# phase90.net
KiCad netlist of a schematic drawn in EAGLE
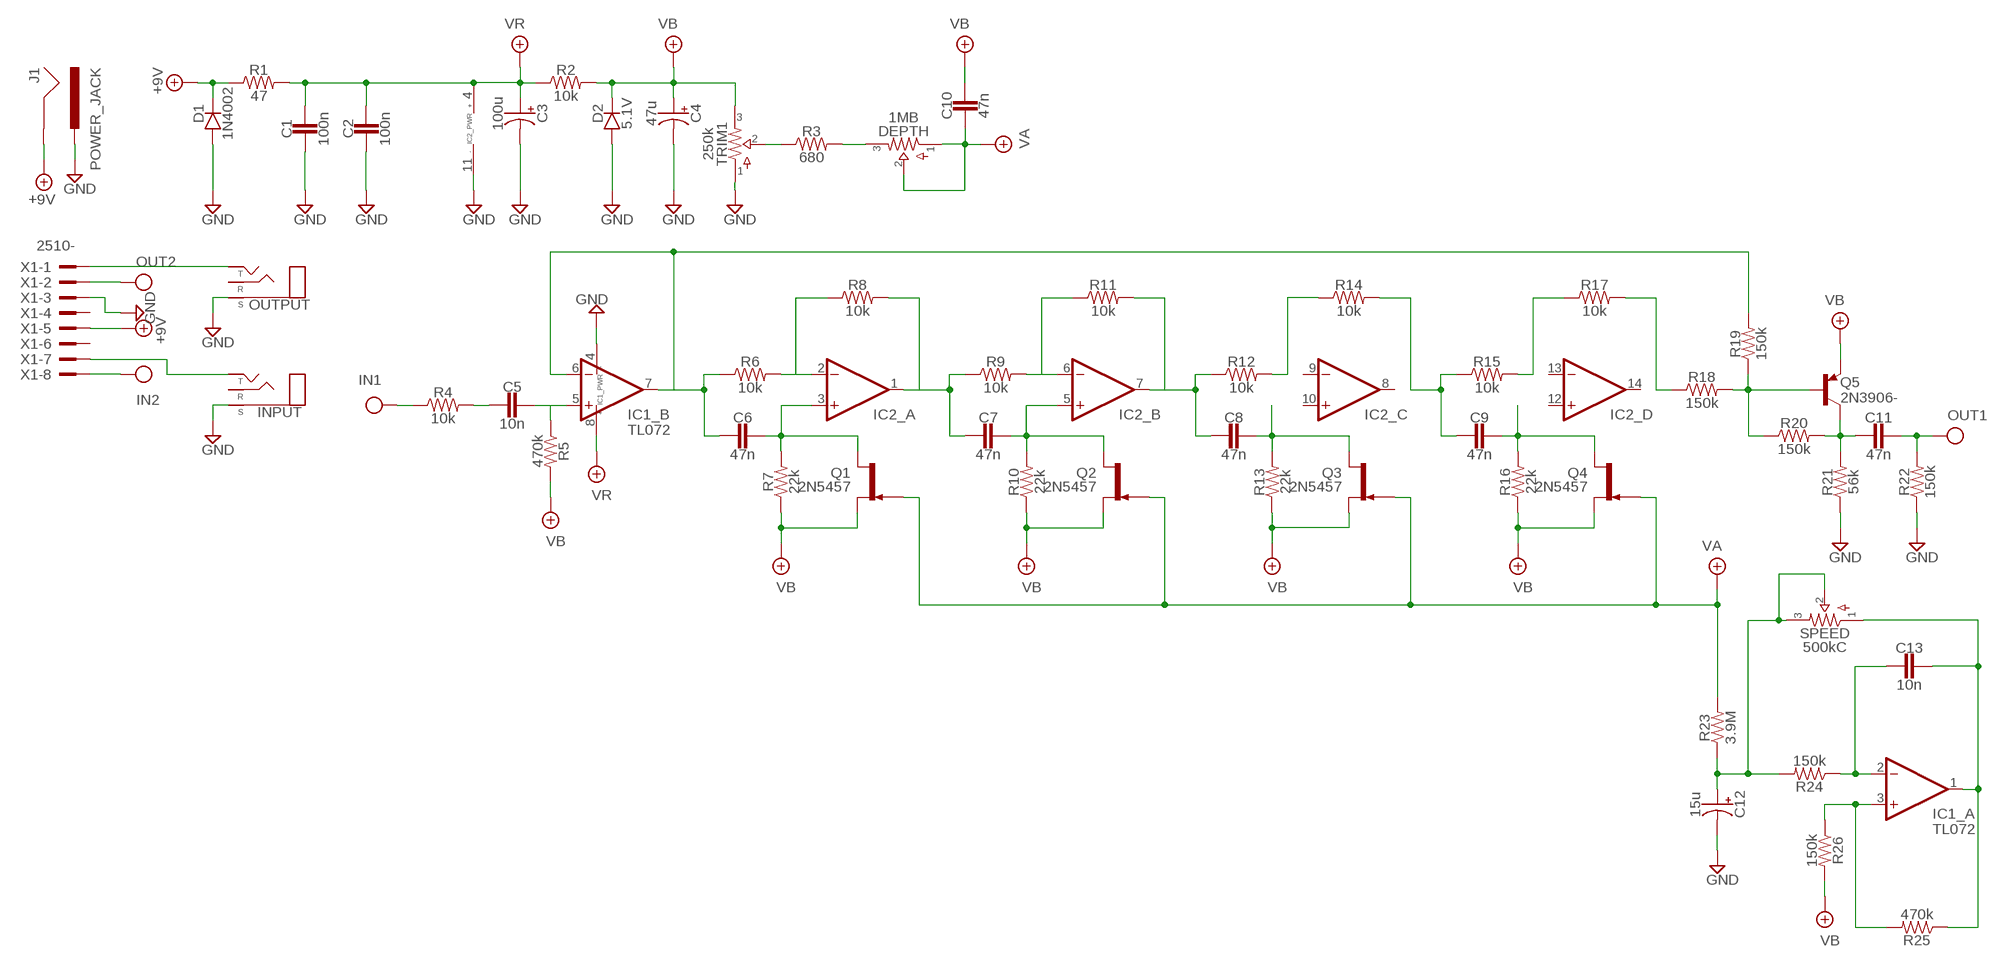
[diagram p0: schematic, sheet 1]

(export (version "E")
  (design (tool "Eeschema 10.0.6"))
  (components
    (comp (ref "C1")
      (value "100n")
      (footprint "eagle-import:050X030_025_2")
      (libsource (lib "eagle-import") (part "CER/FILM2"))
    )
    (comp (ref "C2")
      (value "100n")
      (footprint "eagle-import:050X030_025_2")
      (libsource (lib "eagle-import") (part "CER/FILM2"))
    )
    (comp (ref "C3")
      (value "100u")
      (footprint "eagle-import:050_020")
      (libsource (lib "eagle-import") (part "0500"))
    )
    (comp (ref "C4")
      (value "47u")
      (footprint "eagle-import:050_020")
      (libsource (lib "eagle-import") (part "0500"))
    )
    (comp (ref "C5")
      (value "10n")
      (footprint "eagle-import:BOX_SMALL")
      (libsource (lib "eagle-import") (part "CER/FILMBOX.1"))
    )
    (comp (ref "C6")
      (value "47n")
      (footprint "eagle-import:BOX_SMALL")
      (libsource (lib "eagle-import") (part "CER/FILMBOX.1"))
    )
    (comp (ref "C7")
      (value "47n")
      (footprint "eagle-import:BOX_SMALL")
      (libsource (lib "eagle-import") (part "CER/FILMBOX.1"))
    )
    (comp (ref "C8")
      (value "47n")
      (footprint "eagle-import:BOX_SMALL")
      (libsource (lib "eagle-import") (part "CER/FILMBOX.1"))
    )
    (comp (ref "C9")
      (value "47n")
      (footprint "eagle-import:BOX_SMALL")
      (libsource (lib "eagle-import") (part "CER/FILMBOX.1"))
    )
    (comp (ref "C10")
      (value "47n")
      (footprint "eagle-import:BOX_SMALL")
      (libsource (lib "eagle-import") (part "CER/FILMBOX.1"))
    )
    (comp (ref "C11")
      (value "47n")
      (footprint "eagle-import:BOX_SMALL")
      (libsource (lib "eagle-import") (part "CER/FILMBOX.1"))
    )
    (comp (ref "C12")
      (value "15u")
      (footprint "eagle-import:050_020_1")
      (libsource (lib "eagle-import") (part "0501"))
    )
    (comp (ref "C13")
      (value "10n")
      (footprint "eagle-import:BOX_SMALL")
      (libsource (lib "eagle-import") (part "CER/FILMBOX.1"))
    )
    (comp (ref "D1")
      (value "1N4002")
      (footprint "eagle-import:DO41-2")
      (libsource (lib "eagle-import") (part "DO41.2"))
    )
    (comp (ref "D2")
      (value "5.1V")
      (footprint "eagle-import:DO41-2")
      (libsource (lib "eagle-import") (part "DO41.2"))
    )
    (comp (ref "DEPTH")
      (value "1MB")
      (footprint "eagle-import:16MM")
      (libsource (lib "eagle-import") (part "POTS16MM"))
    )
    (comp (ref "IC1")
      (value "TL072")
      (footprint "eagle-import:DIL0")
      (libsource (lib "eagle-import") (part "DUALTH"))
    )
    (comp (ref "IC2")
      (value "QUADTH")
      (footprint "eagle-import:DIL14")
      (libsource (lib "eagle-import") (part "QUADTH"))
    )
    (comp (ref "INPUT")
      (value "STEREONMJ")
      (footprint "eagle-import:NMJ6HCD2")
      (libsource (lib "eagle-import") (part "STEREONMJ"))
    )
    (comp (ref "J1")
      (value "POWER_JACK")
      (footprint "eagle-import:POWER_JACK_PTH")
      (libsource (lib "eagle-import") (part "POWER_JACK"))
    )
    (comp (ref "OUTPUT")
      (value "STEREONMJ")
      (footprint "eagle-import:NMJ6HCD2")
      (libsource (lib "eagle-import") (part "STEREONMJ"))
    )
    (comp (ref "Q1")
      (value "2N5457")
      (footprint "eagle-import:TO92-")
      (libsource (lib "eagle-import") (part "2N5457"))
    )
    (comp (ref "Q2")
      (value "2N5457")
      (footprint "eagle-import:TO92-")
      (libsource (lib "eagle-import") (part "2N5457"))
    )
    (comp (ref "Q3")
      (value "2N5457")
      (footprint "eagle-import:TO92-")
      (libsource (lib "eagle-import") (part "2N5457"))
    )
    (comp (ref "Q4")
      (value "2N5457")
      (footprint "eagle-import:TO92-")
      (libsource (lib "eagle-import") (part "2N5457"))
    )
    (comp (ref "Q5")
      (value "2N3906-")
      (footprint "eagle-import:TO92-")
      (libsource (lib "eagle-import") (part "2N3906-"))
    )
    (comp (ref "R1")
      (value "47")
      (footprint "eagle-import:R0207_3")
      (libsource (lib "eagle-import") (part "R_.3B"))
    )
    (comp (ref "R2")
      (value "10k")
      (footprint "eagle-import:R0207_3")
      (libsource (lib "eagle-import") (part "R_.3B"))
    )
    (comp (ref "R3")
      (value "680")
      (footprint "eagle-import:R0207_3")
      (libsource (lib "eagle-import") (part "R_.3B"))
    )
    (comp (ref "R4")
      (value "10k")
      (footprint "eagle-import:R0207_3")
      (libsource (lib "eagle-import") (part "R_.3B"))
    )
    (comp (ref "R5")
      (value "470k")
      (footprint "eagle-import:R0207_3")
      (libsource (lib "eagle-import") (part "R_.3B"))
    )
    (comp (ref "R6")
      (value "10k")
      (footprint "eagle-import:R0207_3")
      (libsource (lib "eagle-import") (part "R_.3B"))
    )
    (comp (ref "R7")
      (value "22k")
      (footprint "eagle-import:R0207_3")
      (libsource (lib "eagle-import") (part "R_.3B"))
    )
    (comp (ref "R8")
      (value "10k")
      (footprint "eagle-import:R0207_3")
      (libsource (lib "eagle-import") (part "R_.3B"))
    )
    (comp (ref "R9")
      (value "10k")
      (footprint "eagle-import:R0207_3")
      (libsource (lib "eagle-import") (part "R_.3B"))
    )
    (comp (ref "R10")
      (value "22k")
      (footprint "eagle-import:R0207_3")
      (libsource (lib "eagle-import") (part "R_.3B"))
    )
    (comp (ref "R11")
      (value "10k")
      (footprint "eagle-import:R0207_3")
      (libsource (lib "eagle-import") (part "R_.3B"))
    )
    (comp (ref "R12")
      (value "10k")
      (footprint "eagle-import:R0207_3")
      (libsource (lib "eagle-import") (part "R_.3B"))
    )
    (comp (ref "R13")
      (value "22k")
      (footprint "eagle-import:R0207_3")
      (libsource (lib "eagle-import") (part "R_.3B"))
    )
    (comp (ref "R14")
      (value "10k")
      (footprint "eagle-import:R0207_3")
      (libsource (lib "eagle-import") (part "R_.3B"))
    )
    (comp (ref "R15")
      (value "10k")
      (footprint "eagle-import:R0207_3")
      (libsource (lib "eagle-import") (part "R_.3B"))
    )
    (comp (ref "R16")
      (value "22k")
      (footprint "eagle-import:R0207_3")
      (libsource (lib "eagle-import") (part "R_.3B"))
    )
    (comp (ref "R17")
      (value "10k")
      (footprint "eagle-import:R0207_3")
      (libsource (lib "eagle-import") (part "R_.3B"))
    )
    (comp (ref "R18")
      (value "150k")
      (footprint "eagle-import:R0207_3")
      (libsource (lib "eagle-import") (part "R_.3B"))
    )
    (comp (ref "R19")
      (value "150k")
      (footprint "eagle-import:R0207_3")
      (libsource (lib "eagle-import") (part "R_.3B"))
    )
    (comp (ref "R20")
      (value "150k")
      (footprint "eagle-import:R0207_3")
      (libsource (lib "eagle-import") (part "R_.3B"))
    )
    (comp (ref "R21")
      (value "56k")
      (footprint "eagle-import:R0207_3")
      (libsource (lib "eagle-import") (part "R_.3B"))
    )
    (comp (ref "R22")
      (value "150k")
      (footprint "eagle-import:R0207_3")
      (libsource (lib "eagle-import") (part "R_.3B"))
    )
    (comp (ref "R23")
      (value "3.9M")
      (footprint "eagle-import:R0207_3")
      (libsource (lib "eagle-import") (part "R_.3B"))
    )
    (comp (ref "R24")
      (value "150k")
      (footprint "eagle-import:R0207_3")
      (libsource (lib "eagle-import") (part "R_.3B"))
    )
    (comp (ref "R25")
      (value "470k")
      (footprint "eagle-import:R0207_3")
      (libsource (lib "eagle-import") (part "R_.3B"))
    )
    (comp (ref "R26")
      (value "150k")
      (footprint "eagle-import:R0207_3")
      (libsource (lib "eagle-import") (part "R_.3B"))
    )
    (comp (ref "SPEED")
      (value "500kC")
      (footprint "eagle-import:16MM")
      (libsource (lib "eagle-import") (part "POTS16MM"))
    )
    (comp (ref "TRIM1")
      (value "250k")
      (footprint "eagle-import:RTRIM3296W")
      (libsource (lib "eagle-import") (part "POTSTEST"))
    )
    (comp (ref "X1")
      (value "2510-")
      (footprint "eagle-import:PAK100_2500-10")
      (fields (field (name "MF") "3M") (field (name "MPN") "2510-6002UB"))
      (libsource (lib "eagle-import") (part "2510-"))
    )
  )
  (nets
    (net (code "1") (name "+9V") (class "Default")
      (node (ref "D1") (pin "C") (pinfunction "C_C") (pintype "passive"))
      (node (ref "J1") (pin "GND") (pinfunction "GND_GND") (pintype "bidirectional"))
      (node (ref "R1") (pin "1") (pinfunction "1_1") (pintype "passive"))
      (node (ref "X1") (pin "5") (pinfunction "KL_5") (pintype "passive"))
    )
    (net (code "2") (name "GND") (class "Default")
      (node (ref "C1") (pin "2") (pinfunction "2_2") (pintype "passive"))
      (node (ref "C12") (pin "-") (pinfunction "-_-") (pintype "passive"))
      (node (ref "C2") (pin "2") (pinfunction "2_2") (pintype "passive"))
      (node (ref "C3") (pin "-") (pinfunction "-_-") (pintype "passive"))
      (node (ref "C4") (pin "-") (pinfunction "-_-") (pintype "passive"))
      (node (ref "D1") (pin "A") (pinfunction "A_A") (pintype "passive"))
      (node (ref "D2") (pin "A") (pinfunction "A_A") (pintype "passive"))
      (node (ref "IC1") (pin "4") (pinfunction "V-_4") (pintype "power_in"))
      (node (ref "IC2") (pin "11") (pinfunction "V-_11") (pintype "power_in"))
      (node (ref "INPUT") (pin "S") (pinfunction "S_S") (pintype "passive"))
      (node (ref "J1") (pin "PWR") (pinfunction "PWR_PWR") (pintype "bidirectional"))
      (node (ref "OUTPUT") (pin "S") (pinfunction "S_S") (pintype "passive"))
      (node (ref "R21") (pin "1") (pinfunction "1_1") (pintype "passive"))
      (node (ref "R22") (pin "1") (pinfunction "1_1") (pintype "passive"))
      (node (ref "TRIM1") (pin "1") (pinfunction "1_1") (pintype "passive"))
      (node (ref "X1") (pin "3") (pinfunction "KL_3") (pintype "passive"))
    )
    (net (code "3") (name "IN") (class "Default")
      (node (ref "R4") (pin "1") (pinfunction "1_1") (pintype "passive"))
      (node (ref "X1") (pin "8") (pinfunction "KL_8") (pintype "passive"))
    )
    (net (code "4") (name "Net-(C5-Pad2)") (class "Default")
      (node (ref "C5") (pin "2") (pinfunction "2_2") (pintype "passive"))
      (node (ref "R4") (pin "2") (pinfunction "2_2") (pintype "passive"))
    )
    (net (code "5") (name "Net-(C9-Pad2)") (class "Default")
      (node (ref "C9") (pin "2") (pinfunction "2_2") (pintype "passive"))
      (node (ref "R14") (pin "2") (pinfunction "2_2") (pintype "passive"))
      (node (ref "R15") (pin "1") (pinfunction "1_1") (pintype "passive"))
    )
    (net (code "6") (name "Net-(C12-Pad+)") (class "Default")
      (node (ref "C12") (pin "+") (pinfunction "+_+") (pintype "passive"))
      (node (ref "R23") (pin "1") (pinfunction "1_1") (pintype "passive"))
      (node (ref "R24") (pin "2") (pinfunction "2_2") (pintype "passive"))
      (node (ref "SPEED") (pin "2") (pinfunction "2_2") (pintype "passive"))
      (node (ref "SPEED") (pin "3") (pinfunction "3_3") (pintype "passive"))
    )
    (net (code "7") (name "Net-(DEPTH-Pad3)") (class "Default")
      (node (ref "DEPTH") (pin "3") (pinfunction "3_3") (pintype "passive"))
      (node (ref "R3") (pin "2") (pinfunction "2_2") (pintype "passive"))
    )
    (net (code "8") (name "Net-(IC1A-+IN)") (class "Default")
      (node (ref "IC1") (pin "3") (pinfunction "+IN_3") (pintype "input"))
      (node (ref "R25") (pin "2") (pinfunction "2_2") (pintype "passive"))
      (node (ref "R26") (pin "1") (pinfunction "1_1") (pintype "passive"))
    )
    (net (code "9") (name "Net-(IC1A--IN)") (class "Default")
      (node (ref "C13") (pin "2") (pinfunction "2_2") (pintype "passive"))
      (node (ref "IC1") (pin "2") (pinfunction "-IN_2") (pintype "input"))
      (node (ref "R24") (pin "1") (pinfunction "1_1") (pintype "passive"))
    )
    (net (code "10") (name "Net-(IC1A-OUT)") (class "Default")
      (node (ref "C13") (pin "1") (pinfunction "1_1") (pintype "passive"))
      (node (ref "IC1") (pin "1") (pinfunction "OUT_1") (pintype "output"))
      (node (ref "R25") (pin "1") (pinfunction "1_1") (pintype "passive"))
      (node (ref "SPEED") (pin "1") (pinfunction "1_1") (pintype "passive"))
    )
    (net (code "11") (name "Net-(IC1B-+IN)") (class "Default")
      (node (ref "C5") (pin "1") (pinfunction "1_1") (pintype "passive"))
      (node (ref "IC1") (pin "5") (pinfunction "+IN_5") (pintype "input"))
      (node (ref "R5") (pin "1") (pinfunction "1_1") (pintype "passive"))
    )
    (net (code "12") (name "Net-(IC1B--IN)") (class "Default")
      (node (ref "C6") (pin "2") (pinfunction "2_2") (pintype "passive"))
      (node (ref "IC1") (pin "6") (pinfunction "-IN_6") (pintype "input"))
      (node (ref "IC1") (pin "7") (pinfunction "OUT_7") (pintype "output"))
      (node (ref "R19") (pin "2") (pinfunction "2_2") (pintype "passive"))
      (node (ref "R6") (pin "1") (pinfunction "1_1") (pintype "passive"))
    )
    (net (code "13") (name "Net-(IC2A-+IN)") (class "Default")
      (node (ref "C6") (pin "1") (pinfunction "1_1") (pintype "passive"))
      (node (ref "IC2") (pin "3") (pinfunction "+IN_3") (pintype "input"))
      (node (ref "Q1") (pin "3") (pinfunction "D_3") (pintype "passive"))
      (node (ref "R7") (pin "2") (pinfunction "2_2") (pintype "passive"))
    )
    (net (code "14") (name "Net-(IC2A--IN)") (class "Default")
      (node (ref "IC2") (pin "2") (pinfunction "-IN_2") (pintype "input"))
      (node (ref "R6") (pin "2") (pinfunction "2_2") (pintype "passive"))
      (node (ref "R8") (pin "1") (pinfunction "1_1") (pintype "passive"))
    )
    (net (code "15") (name "Net-(IC2A-OUT)") (class "Default")
      (node (ref "C7") (pin "2") (pinfunction "2_2") (pintype "passive"))
      (node (ref "IC2") (pin "1") (pinfunction "OUT_1") (pintype "output"))
      (node (ref "R8") (pin "2") (pinfunction "2_2") (pintype "passive"))
      (node (ref "R9") (pin "1") (pinfunction "1_1") (pintype "passive"))
    )
    (net (code "16") (name "Net-(IC2B-+IN)") (class "Default")
      (node (ref "C7") (pin "1") (pinfunction "1_1") (pintype "passive"))
      (node (ref "IC2") (pin "5") (pinfunction "+IN_5") (pintype "input"))
      (node (ref "Q2") (pin "3") (pinfunction "D_3") (pintype "passive"))
      (node (ref "R10") (pin "2") (pinfunction "2_2") (pintype "passive"))
    )
    (net (code "17") (name "Net-(IC2B--IN)") (class "Default")
      (node (ref "IC2") (pin "6") (pinfunction "-IN_6") (pintype "input"))
      (node (ref "R11") (pin "1") (pinfunction "1_1") (pintype "passive"))
      (node (ref "R9") (pin "2") (pinfunction "2_2") (pintype "passive"))
    )
    (net (code "18") (name "Net-(IC2B-OUT)") (class "Default")
      (node (ref "C8") (pin "2") (pinfunction "2_2") (pintype "passive"))
      (node (ref "IC2") (pin "7") (pinfunction "OUT_7") (pintype "output"))
      (node (ref "R11") (pin "2") (pinfunction "2_2") (pintype "passive"))
      (node (ref "R12") (pin "1") (pinfunction "1_1") (pintype "passive"))
    )
    (net (code "19") (name "Net-(Q3-D)") (class "Default")
      (node (ref "C8") (pin "1") (pinfunction "1_1") (pintype "passive"))
      (node (ref "Q3") (pin "3") (pinfunction "D_3") (pintype "passive"))
      (node (ref "R13") (pin "2") (pinfunction "2_2") (pintype "passive"))
    )
    (net (code "20") (name "Net-(Q4-D)") (class "Default")
      (node (ref "C9") (pin "1") (pinfunction "1_1") (pintype "passive"))
      (node (ref "Q4") (pin "3") (pinfunction "D_3") (pintype "passive"))
      (node (ref "R16") (pin "2") (pinfunction "2_2") (pintype "passive"))
    )
    (net (code "21") (name "Net-(Q5-B)") (class "Default")
      (node (ref "Q5") (pin "2") (pinfunction "B_2") (pintype "passive"))
      (node (ref "R18") (pin "2") (pinfunction "2_2") (pintype "passive"))
      (node (ref "R19") (pin "1") (pinfunction "1_1") (pintype "passive"))
      (node (ref "R20") (pin "1") (pinfunction "1_1") (pintype "passive"))
    )
    (net (code "22") (name "Net-(Q5-C)") (class "Default")
      (node (ref "C11") (pin "2") (pinfunction "2_2") (pintype "passive"))
      (node (ref "Q5") (pin "1") (pinfunction "C_1") (pintype "passive"))
      (node (ref "R20") (pin "2") (pinfunction "2_2") (pintype "passive"))
      (node (ref "R21") (pin "2") (pinfunction "2_2") (pintype "passive"))
    )
    (net (code "23") (name "Net-(R3-Pad1)") (class "Default")
      (node (ref "R3") (pin "1") (pinfunction "1_1") (pintype "passive"))
      (node (ref "TRIM1") (pin "2") (pinfunction "2_2") (pintype "passive"))
    )
    (net (code "24") (name "Net-(R12-Pad2)") (class "Default")
      (node (ref "R12") (pin "2") (pinfunction "2_2") (pintype "passive"))
      (node (ref "R14") (pin "1") (pinfunction "1_1") (pintype "passive"))
    )
    (net (code "25") (name "Net-(R15-Pad2)") (class "Default")
      (node (ref "R15") (pin "2") (pinfunction "2_2") (pintype "passive"))
      (node (ref "R17") (pin "1") (pinfunction "1_1") (pintype "passive"))
    )
    (net (code "26") (name "Net-(R17-Pad2)") (class "Default")
      (node (ref "R17") (pin "2") (pinfunction "2_2") (pintype "passive"))
      (node (ref "R18") (pin "1") (pinfunction "1_1") (pintype "passive"))
    )
    (net (code "27") (name "Net-(X1A-KL)") (class "Default")
      (node (ref "OUTPUT") (pin "T") (pinfunction "T_T") (pintype "passive"))
      (node (ref "X1") (pin "1") (pinfunction "KL_1") (pintype "passive"))
    )
    (net (code "28") (name "Net-(X1G-KL)") (class "Default")
      (node (ref "INPUT") (pin "T") (pinfunction "T_T") (pintype "passive"))
      (node (ref "X1") (pin "7") (pinfunction "KL_7") (pintype "passive"))
    )
    (net (code "29") (name "OUT") (class "Default")
      (node (ref "C11") (pin "1") (pinfunction "1_1") (pintype "passive"))
      (node (ref "R22") (pin "2") (pinfunction "2_2") (pintype "passive"))
      (node (ref "X1") (pin "2") (pinfunction "KL_2") (pintype "passive"))
    )
    (net (code "30") (name "VA") (class "Default")
      (node (ref "C10") (pin "2") (pinfunction "2_2") (pintype "passive"))
      (node (ref "DEPTH") (pin "1") (pinfunction "1_1") (pintype "passive"))
      (node (ref "DEPTH") (pin "2") (pinfunction "2_2") (pintype "passive"))
      (node (ref "Q1") (pin "1") (pinfunction "G_1") (pintype "passive"))
      (node (ref "Q2") (pin "1") (pinfunction "G_1") (pintype "passive"))
      (node (ref "Q3") (pin "1") (pinfunction "G_1") (pintype "passive"))
      (node (ref "Q4") (pin "1") (pinfunction "G_1") (pintype "passive"))
      (node (ref "R23") (pin "2") (pinfunction "2_2") (pintype "passive"))
    )
    (net (code "31") (name "VB") (class "Default")
      (node (ref "C10") (pin "1") (pinfunction "1_1") (pintype "passive"))
      (node (ref "C4") (pin "+") (pinfunction "+_+") (pintype "passive"))
      (node (ref "D2") (pin "C") (pinfunction "C_C") (pintype "passive"))
      (node (ref "Q1") (pin "2") (pinfunction "S_2") (pintype "passive"))
      (node (ref "Q2") (pin "2") (pinfunction "S_2") (pintype "passive"))
      (node (ref "Q3") (pin "2") (pinfunction "S_2") (pintype "passive"))
      (node (ref "Q4") (pin "2") (pinfunction "S_2") (pintype "passive"))
      (node (ref "Q5") (pin "3") (pinfunction "E_3") (pintype "passive"))
      (node (ref "R10") (pin "1") (pinfunction "1_1") (pintype "passive"))
      (node (ref "R13") (pin "1") (pinfunction "1_1") (pintype "passive"))
      (node (ref "R16") (pin "1") (pinfunction "1_1") (pintype "passive"))
      (node (ref "R2") (pin "2") (pinfunction "2_2") (pintype "passive"))
      (node (ref "R26") (pin "2") (pinfunction "2_2") (pintype "passive"))
      (node (ref "R5") (pin "2") (pinfunction "2_2") (pintype "passive"))
      (node (ref "R7") (pin "1") (pinfunction "1_1") (pintype "passive"))
      (node (ref "TRIM1") (pin "3") (pinfunction "3_3") (pintype "passive"))
    )
    (net (code "32") (name "VR") (class "Default")
      (node (ref "C1") (pin "1") (pinfunction "1_1") (pintype "passive"))
      (node (ref "C2") (pin "1") (pinfunction "1_1") (pintype "passive"))
      (node (ref "C3") (pin "+") (pinfunction "+_+") (pintype "passive"))
      (node (ref "IC1") (pin "8") (pinfunction "V+_8") (pintype "power_in"))
      (node (ref "IC2") (pin "4") (pinfunction "V+_4") (pintype "power_in"))
      (node (ref "R1") (pin "2") (pinfunction "2_2") (pintype "passive"))
      (node (ref "R2") (pin "1") (pinfunction "1_1") (pintype "passive"))
    )
    (net (code "33") (name "unconnected-(IC2C-+IN-Pad10)") (class "Default")
      (node (ref "IC2") (pin "10") (pinfunction "+IN_10") (pintype "input"))
    )
    (net (code "34") (name "unconnected-(IC2C--IN-Pad9)") (class "Default")
      (node (ref "IC2") (pin "9") (pinfunction "-IN_9") (pintype "input"))
    )
    (net (code "35") (name "unconnected-(IC2C-OUT-Pad8)") (class "Default")
      (node (ref "IC2") (pin "8") (pinfunction "OUT_8") (pintype "output"))
    )
    (net (code "36") (name "unconnected-(IC2D-+IN-Pad12)") (class "Default")
      (node (ref "IC2") (pin "12") (pinfunction "+IN_12") (pintype "input"))
    )
    (net (code "37") (name "unconnected-(IC2D--IN-Pad13)") (class "Default")
      (node (ref "IC2") (pin "13") (pinfunction "-IN_13") (pintype "input"))
    )
    (net (code "38") (name "unconnected-(IC2D-OUT-Pad14)") (class "Default")
      (node (ref "IC2") (pin "14") (pinfunction "OUT_14") (pintype "output"))
    )
    (net (code "39") (name "unconnected-(INPUT-PadR)") (class "Default")
      (node (ref "INPUT") (pin "R") (pinfunction "R_R") (pintype "passive"))
    )
    (net (code "40") (name "unconnected-(OUTPUT-PadR)") (class "Default")
      (node (ref "OUTPUT") (pin "R") (pinfunction "R_R") (pintype "passive"))
    )
    (net (code "41") (name "unconnected-(X1D-KL-Pad4)") (class "Default")
      (node (ref "X1") (pin "4") (pinfunction "KL_4") (pintype "passive"))
    )
    (net (code "42") (name "unconnected-(X1F-KL-Pad6)") (class "Default")
      (node (ref "X1") (pin "6") (pinfunction "KL_6") (pintype "passive"))
    )
  )
)
